# AstableMultivibrator-PNP-CapPol.net
KiCad netlist of a schematic drawn in EAGLE
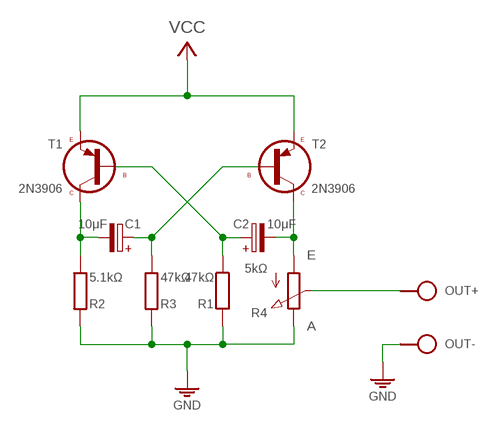
[diagram p0: schematic, sheet 1]

(export (version "E")
  (design (tool "Eeschema 10.0.6"))
  (components
    (comp (ref "C1")
      (value "10μF")
      (footprint "eagle-import:E2,5-4")
      (libsource (lib "eagle-import") (part "CPOL-HE2,5-4"))
    )
    (comp (ref "C2")
      (value "10μF")
      (footprint "eagle-import:E2,5-4")
      (libsource (lib "eagle-import") (part "CPOL-HE2,5-4"))
    )
    (comp (ref "J1")
      (value "VCC_GNDPWR-L")
      (footprint "eagle-import:PWR-L")
      (libsource (lib "eagle-import") (part "VCC_GNDPWR-L"))
    )
    (comp (ref "OUT")
      (value "SPAD+--+")
      (footprint "eagle-import:SPAD-+")
      (libsource (lib "eagle-import") (part "SPAD+--+"))
    )
    (comp (ref "R1")
      (value "47kΩ")
      (footprint "eagle-import:0204_10-V")
      (libsource (lib "eagle-import") (part "R0204/10-V"))
    )
    (comp (ref "R2")
      (value "5.1kΩ")
      (footprint "eagle-import:0204_10-V")
      (libsource (lib "eagle-import") (part "R0204/10-V"))
    )
    (comp (ref "R3")
      (value "47kΩ")
      (footprint "eagle-import:0204_10-V")
      (libsource (lib "eagle-import") (part "R0204/10-V"))
    )
    (comp (ref "R4")
      (value "5kΩ")
      (footprint "eagle-import:TRIM-POT")
      (libsource (lib "eagle-import") (part "POT-TRIM"))
    )
    (comp (ref "T1")
      (value "2N3906")
      (footprint "eagle-import:TO92")
      (libsource (lib "eagle-import") (part "2N3906"))
    )
    (comp (ref "T2")
      (value "2N3906")
      (footprint "eagle-import:TO92")
      (libsource (lib "eagle-import") (part "2N3906"))
    )
  )
  (nets
    (net (code "1") (name "GND") (class "Default")
      (node (ref "J1") (pin "1") (pinfunction "GND_1") (pintype "power_in"))
      (node (ref "OUT") (pin "1") (pinfunction "P$1_1") (pintype "passive"))
      (node (ref "R1") (pin "1") (pinfunction "2_1") (pintype "passive"))
      (node (ref "R2") (pin "1") (pinfunction "2_1") (pintype "passive"))
      (node (ref "R3") (pin "1") (pinfunction "2_1") (pintype "passive"))
      (node (ref "R4") (pin "E") (pinfunction "E_E") (pintype "passive"))
    )
    (net (code "2") (name "Net-(J1A-VCC)") (class "Default")
      (node (ref "J1") (pin "2") (pinfunction "VCC_2") (pintype "power_in"))
      (node (ref "T1") (pin "1") (pinfunction "E_1") (pintype "passive"))
      (node (ref "T2") (pin "1") (pinfunction "E_1") (pintype "passive"))
    )
    (net (code "3") (name "Net-(OUTA-P$1)") (class "Default")
      (node (ref "OUT") (pin "2") (pinfunction "P$1_2") (pintype "passive"))
      (node (ref "R4") (pin "S") (pinfunction "S_S") (pintype "passive"))
    )
    (net (code "4") (name "Net-(R1-1)") (class "Default")
      (node (ref "C2") (pin "+") (pinfunction "+_+") (pintype "passive"))
      (node (ref "R1") (pin "2") (pinfunction "1_2") (pintype "passive"))
      (node (ref "T1") (pin "2") (pinfunction "B_2") (pintype "passive"))
    )
    (net (code "5") (name "Net-(R2-1)") (class "Default")
      (node (ref "C1") (pin "-") (pinfunction "-_-") (pintype "passive"))
      (node (ref "R2") (pin "2") (pinfunction "1_2") (pintype "passive"))
      (node (ref "T1") (pin "3") (pinfunction "C_3") (pintype "passive"))
    )
    (net (code "6") (name "Net-(R3-1)") (class "Default")
      (node (ref "C1") (pin "+") (pinfunction "+_+") (pintype "passive"))
      (node (ref "R3") (pin "2") (pinfunction "1_2") (pintype "passive"))
      (node (ref "T2") (pin "2") (pinfunction "B_2") (pintype "passive"))
    )
    (net (code "7") (name "Net-(T2-C)") (class "Default")
      (node (ref "C2") (pin "-") (pinfunction "-_-") (pintype "passive"))
      (node (ref "R4") (pin "A") (pinfunction "A_A") (pintype "passive"))
      (node (ref "T2") (pin "3") (pinfunction "C_3") (pintype "passive"))
    )
  )
)
